# Ulimate.net
KiCad netlist of a schematic drawn in EAGLE
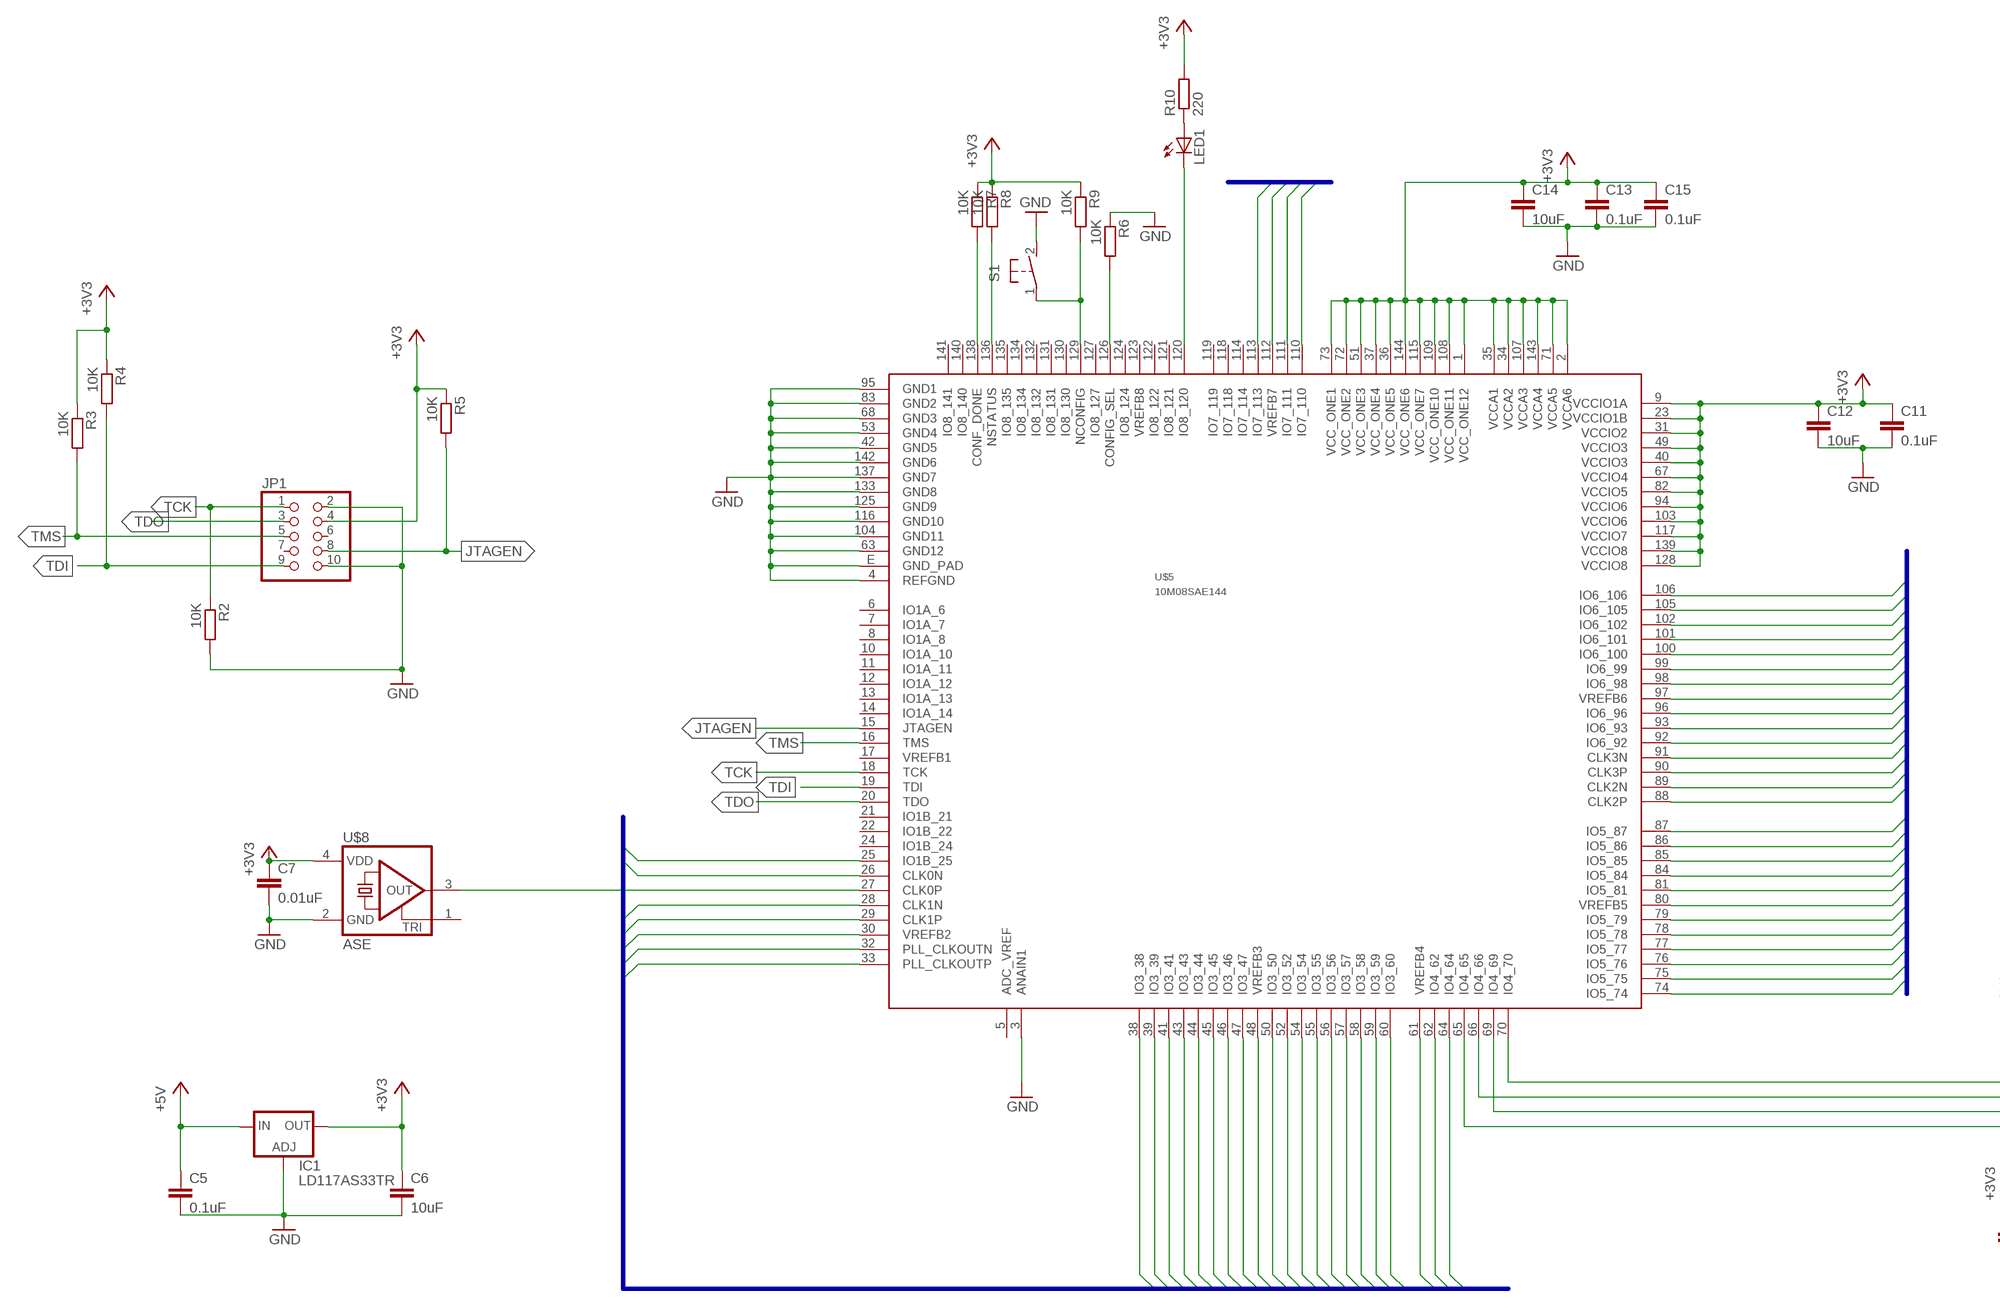
[diagram p0: schematic, sheet 1, part 1 of 2]
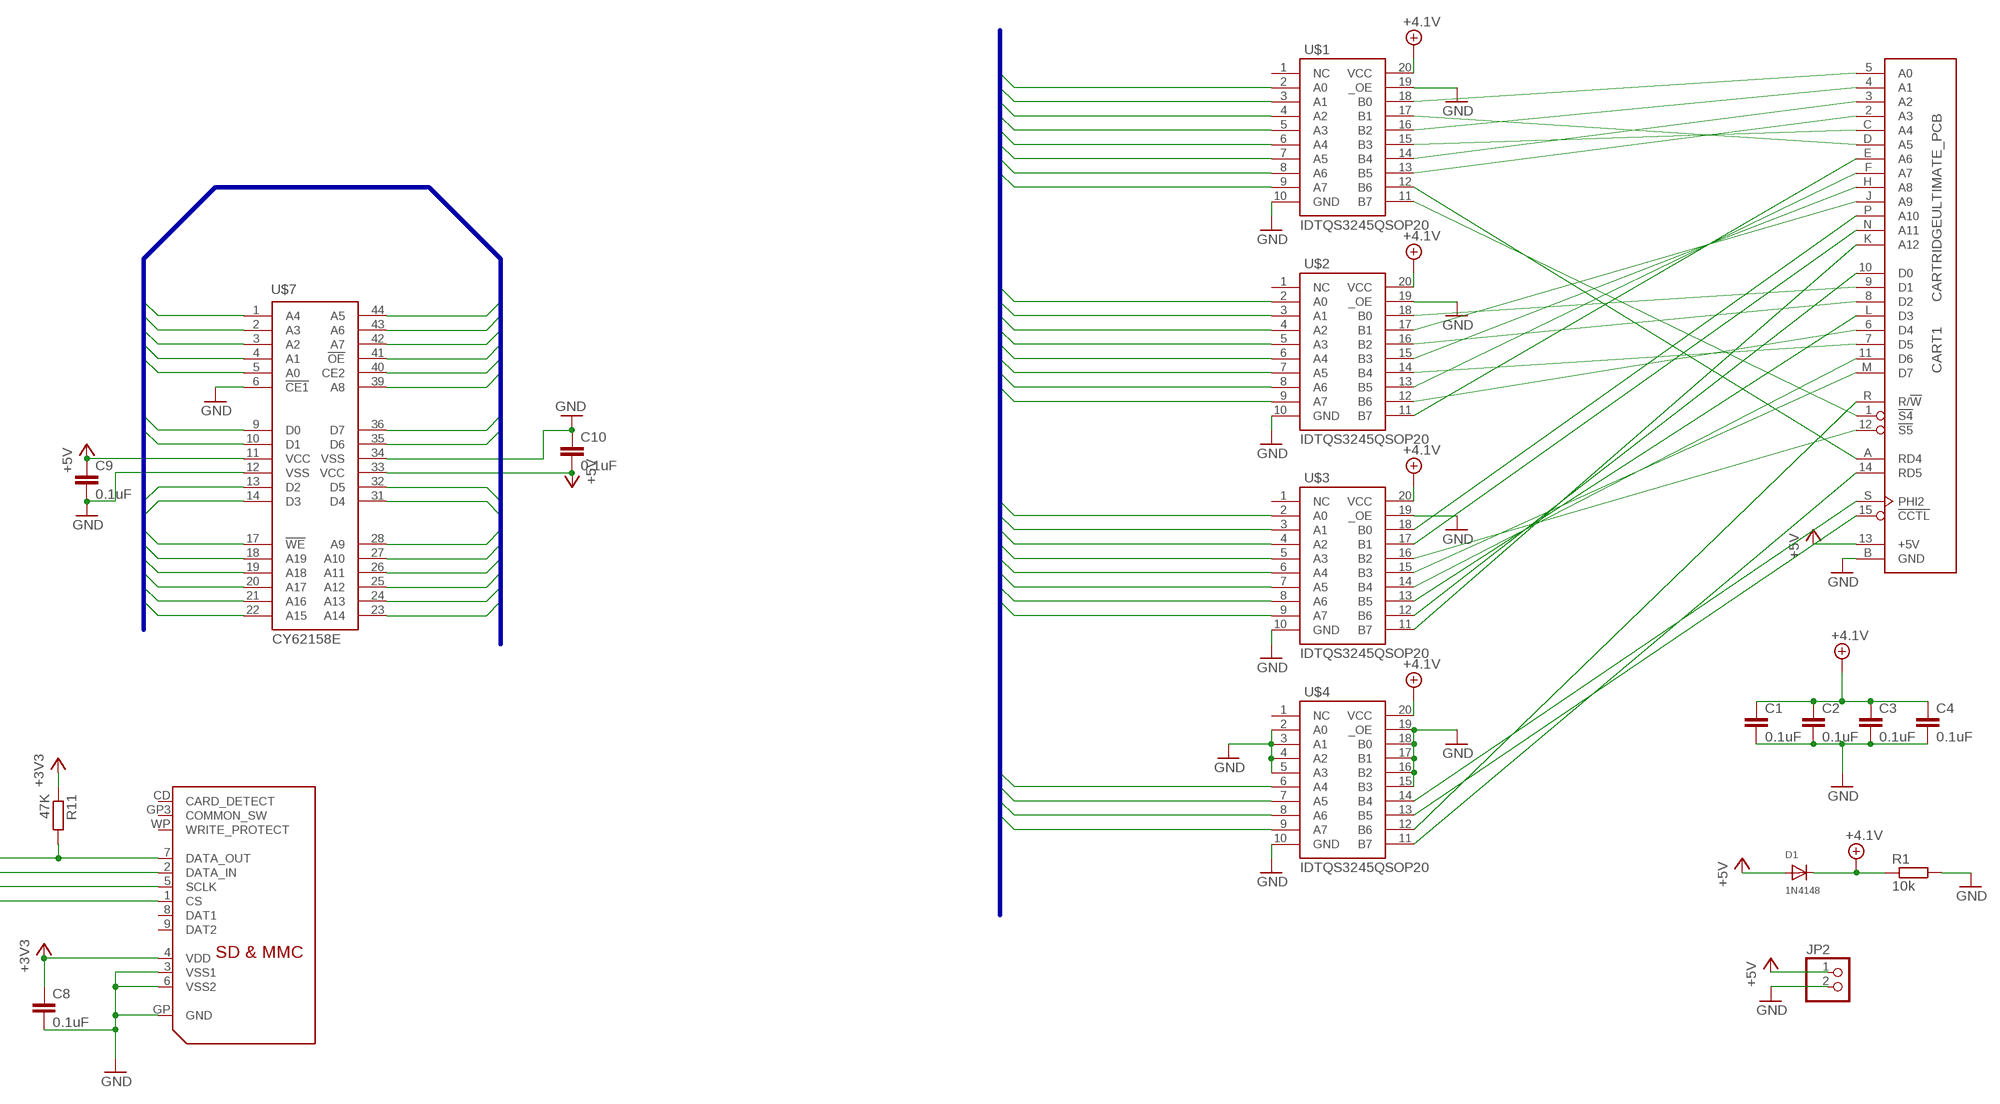
[diagram p1: schematic, sheet 1, part 2 of 2]

(export (version "E")
  (design (tool "Eeschema 10.0.6"))
  (components
    (comp (ref "C1")
      (value "0.1uF")
      (footprint "eagle-import:C0805K")
      (libsource (lib "eagle-import") (part "C-EUC0805K"))
    )
    (comp (ref "C2")
      (value "0.1uF")
      (footprint "eagle-import:C0805K")
      (libsource (lib "eagle-import") (part "C-EUC0805K"))
    )
    (comp (ref "C3")
      (value "0.1uF")
      (footprint "eagle-import:C0805K")
      (libsource (lib "eagle-import") (part "C-EUC0805K"))
    )
    (comp (ref "C4")
      (value "0.1uF")
      (footprint "eagle-import:C0805K")
      (libsource (lib "eagle-import") (part "C-EUC0805K"))
    )
    (comp (ref "C5")
      (value "0.1uF")
      (footprint "eagle-import:C0805K")
      (libsource (lib "eagle-import") (part "C-EUC0805K"))
    )
    (comp (ref "C6")
      (value "10uF")
      (footprint "eagle-import:C0805K")
      (libsource (lib "eagle-import") (part "C-EUC0805K"))
    )
    (comp (ref "C7")
      (value "0.01uF")
      (footprint "eagle-import:C0805K")
      (libsource (lib "eagle-import") (part "C-EUC0805K"))
    )
    (comp (ref "C8")
      (value "0.1uF")
      (footprint "eagle-import:C0805K")
      (libsource (lib "eagle-import") (part "C-EUC0805K"))
    )
    (comp (ref "C9")
      (value "0.1uF")
      (footprint "eagle-import:C0805K")
      (libsource (lib "eagle-import") (part "C-EUC0805K"))
    )
    (comp (ref "C10")
      (value "0.1uF")
      (footprint "eagle-import:C0805K")
      (libsource (lib "eagle-import") (part "C-EUC0805K"))
    )
    (comp (ref "C11")
      (value "0.1uF")
      (footprint "eagle-import:C0805K")
      (libsource (lib "eagle-import") (part "C-EUC0805K"))
    )
    (comp (ref "C12")
      (value "10uF")
      (footprint "eagle-import:C0805K")
      (libsource (lib "eagle-import") (part "C-EUC0805K"))
    )
    (comp (ref "C13")
      (value "0.1uF")
      (footprint "eagle-import:C0805K")
      (libsource (lib "eagle-import") (part "C-EUC0805K"))
    )
    (comp (ref "C14")
      (value "10uF")
      (footprint "eagle-import:C0805K")
      (libsource (lib "eagle-import") (part "C-EUC0805K"))
    )
    (comp (ref "C15")
      (value "0.1uF")
      (footprint "eagle-import:C0805K")
      (libsource (lib "eagle-import") (part "C-EUC0805K"))
    )
    (comp (ref "CART1")
      (value "CARTRIDGEULTIMATE_PCB")
      (footprint "eagle-import:CART_ULTIMATE")
      (libsource (lib "eagle-import") (part "CARTRIDGEULTIMATE_PCB"))
    )
    (comp (ref "D1")
      (value "1N4148")
      (footprint "eagle-import:SOD-123FL")
      (libsource (lib "eagle-import") (part "DIODE_SOD-123FL"))
    )
    (comp (ref "IC1")
      (value "LD117AS33TR")
      (footprint "eagle-import:SOT223")
      (libsource (lib "eagle-import") (part "LD117A?S33TR"))
    )
    (comp (ref "JP1")
      (value "PINHD-2X5")
      (footprint "eagle-import:2X05")
      (libsource (lib "eagle-import") (part "PINHD-2X5"))
    )
    (comp (ref "JP2")
      (value "PINHD-1X2")
      (footprint "eagle-import:1X02")
      (libsource (lib "eagle-import") (part "PINHD-1X2"))
    )
    (comp (ref "LED1")
      (value "LEDSML0805")
      (footprint "eagle-import:SML0805")
      (libsource (lib "eagle-import") (part "LEDSML0805"))
    )
    (comp (ref "R1")
      (value "10k")
      (footprint "eagle-import:R0805")
      (libsource (lib "eagle-import") (part "R-EU_R0805"))
    )
    (comp (ref "R2")
      (value "10K")
      (footprint "eagle-import:R0805")
      (libsource (lib "eagle-import") (part "R-EU_R0805"))
    )
    (comp (ref "R3")
      (value "10K")
      (footprint "eagle-import:R0805")
      (libsource (lib "eagle-import") (part "R-EU_R0805"))
    )
    (comp (ref "R4")
      (value "10K")
      (footprint "eagle-import:R0805")
      (libsource (lib "eagle-import") (part "R-EU_R0805"))
    )
    (comp (ref "R5")
      (value "10K")
      (footprint "eagle-import:R0805")
      (libsource (lib "eagle-import") (part "R-EU_R0805"))
    )
    (comp (ref "R6")
      (value "10K")
      (footprint "eagle-import:R0805")
      (libsource (lib "eagle-import") (part "R-EU_R0805"))
    )
    (comp (ref "R7")
      (value "10K")
      (footprint "eagle-import:R0805")
      (libsource (lib "eagle-import") (part "R-EU_R0805"))
    )
    (comp (ref "R8")
      (value "10K")
      (footprint "eagle-import:R0805")
      (libsource (lib "eagle-import") (part "R-EU_R0805"))
    )
    (comp (ref "R9")
      (value "10K")
      (footprint "eagle-import:R0805")
      (libsource (lib "eagle-import") (part "R-EU_R0805"))
    )
    (comp (ref "R10")
      (value "220")
      (footprint "eagle-import:R0805")
      (libsource (lib "eagle-import") (part "R-EU_R0805"))
    )
    (comp (ref "R11")
      (value "47K")
      (footprint "eagle-import:R0805")
      (libsource (lib "eagle-import") (part "R-EU_R0805"))
    )
    (comp (ref "S1")
      (value "31-XXSKINNY")
      (footprint "eagle-import:B3F-31XX-SKINNIER")
      (libsource (lib "eagle-import") (part "31-XXSKINNY"))
    )
    (comp (ref "U$1")
      (value "IDTQS3245QSOP20")
      (footprint "eagle-import:QSOP20")
      (libsource (lib "eagle-import") (part "IDTQS3245QSOP20"))
    )
    (comp (ref "U$2")
      (value "IDTQS3245QSOP20")
      (footprint "eagle-import:QSOP20")
      (libsource (lib "eagle-import") (part "IDTQS3245QSOP20"))
    )
    (comp (ref "U$3")
      (value "IDTQS3245QSOP20")
      (footprint "eagle-import:QSOP20")
      (libsource (lib "eagle-import") (part "IDTQS3245QSOP20"))
    )
    (comp (ref "U$4")
      (value "IDTQS3245QSOP20")
      (footprint "eagle-import:QSOP20")
      (libsource (lib "eagle-import") (part "IDTQS3245QSOP20"))
    )
    (comp (ref "U$5")
      (value "10M08SAE144")
      (footprint "eagle-import:EQFP144")
      (libsource (lib "eagle-import") (part "10M08SAE144"))
    )
    (comp (ref "U$6")
      (value "SDMMC06132")
      (footprint "eagle-import:06132")
      (libsource (lib "eagle-import") (part "SDMMC06132"))
    )
    (comp (ref "U$7")
      (value "CY62158E")
      (footprint "eagle-import:TSOP44-II")
      (libsource (lib "eagle-import") (part "CY62158E"))
    )
    (comp (ref "U$8")
      (value "ASE")
      (footprint "eagle-import:ASE")
      (libsource (lib "eagle-import") (part "ASE"))
    )
  )
  (nets
    (net (code "1") (name "+3V3") (class "Default")
      (node (ref "C11") (pin "1") (pinfunction "1_1") (pintype "passive"))
      (node (ref "C12") (pin "1") (pinfunction "1_1") (pintype "passive"))
      (node (ref "C13") (pin "1") (pinfunction "1_1") (pintype "passive"))
      (node (ref "C14") (pin "1") (pinfunction "1_1") (pintype "passive"))
      (node (ref "C15") (pin "1") (pinfunction "1_1") (pintype "passive"))
      (node (ref "C6") (pin "1") (pinfunction "1_1") (pintype "passive"))
      (node (ref "C7") (pin "1") (pinfunction "1_1") (pintype "passive"))
      (node (ref "C8") (pin "1") (pinfunction "1_1") (pintype "passive"))
      (node (ref "IC1") (pin "4") (pinfunction "OUT_4") (pintype "passive"))
      (node (ref "JP1") (pin "4") (pinfunction "4_4") (pintype "passive"))
      (node (ref "R10") (pin "2") (pinfunction "2_2") (pintype "passive"))
      (node (ref "R11") (pin "1") (pinfunction "1_1") (pintype "passive"))
      (node (ref "R3") (pin "1") (pinfunction "1_1") (pintype "passive"))
      (node (ref "R4") (pin "1") (pinfunction "1_1") (pintype "passive"))
      (node (ref "R5") (pin "1") (pinfunction "1_1") (pintype "passive"))
      (node (ref "R7") (pin "1") (pinfunction "1_1") (pintype "passive"))
      (node (ref "R8") (pin "1") (pinfunction "1_1") (pintype "passive"))
      (node (ref "R9") (pin "1") (pinfunction "1_1") (pintype "passive"))
      (node (ref "U$5") (pin "1") (pinfunction "VCC_ONE12_1") (pintype "bidirectional"))
      (node (ref "U$5") (pin "103") (pinfunction "VCCIO6_103") (pintype "bidirectional"))
      (node (ref "U$5") (pin "107") (pinfunction "VCCA3_107") (pintype "bidirectional"))
      (node (ref "U$5") (pin "108") (pinfunction "VCC_ONE11_108") (pintype "bidirectional"))
      (node (ref "U$5") (pin "109") (pinfunction "VCC_ONE10_109") (pintype "bidirectional"))
      (node (ref "U$5") (pin "115") (pinfunction "VCC_ONE7_115") (pintype "bidirectional"))
      (node (ref "U$5") (pin "117") (pinfunction "VCCIO7_117") (pintype "bidirectional"))
      (node (ref "U$5") (pin "128") (pinfunction "VCCIO8_128") (pintype "bidirectional"))
      (node (ref "U$5") (pin "139") (pinfunction "VCCIO8_139") (pintype "bidirectional"))
      (node (ref "U$5") (pin "143") (pinfunction "VCCA4_143") (pintype "bidirectional"))
      (node (ref "U$5") (pin "144") (pinfunction "VCC_ONE6_144") (pintype "bidirectional"))
      (node (ref "U$5") (pin "2") (pinfunction "VCCA6_2") (pintype "bidirectional"))
      (node (ref "U$5") (pin "23") (pinfunction "VCCIO1B_23") (pintype "bidirectional"))
      (node (ref "U$5") (pin "31") (pinfunction "VCCIO2_31") (pintype "bidirectional"))
      (node (ref "U$5") (pin "34") (pinfunction "VCCA2_34") (pintype "bidirectional"))
      (node (ref "U$5") (pin "35") (pinfunction "VCCA1_35") (pintype "bidirectional"))
      (node (ref "U$5") (pin "36") (pinfunction "VCC_ONE5_36") (pintype "bidirectional"))
      (node (ref "U$5") (pin "37") (pinfunction "VCC_ONE4_37") (pintype "bidirectional"))
      (node (ref "U$5") (pin "40") (pinfunction "VCCIO3_40") (pintype "bidirectional"))
      (node (ref "U$5") (pin "49") (pinfunction "VCCIO3_49") (pintype "bidirectional"))
      (node (ref "U$5") (pin "51") (pinfunction "VCC_ONE3_51") (pintype "bidirectional"))
      (node (ref "U$5") (pin "67") (pinfunction "VCCIO4_67") (pintype "bidirectional"))
      (node (ref "U$5") (pin "71") (pinfunction "VCCA5_71") (pintype "bidirectional"))
      (node (ref "U$5") (pin "72") (pinfunction "VCC_ONE2_72") (pintype "bidirectional"))
      (node (ref "U$5") (pin "73") (pinfunction "VCC_ONE1_73") (pintype "bidirectional"))
      (node (ref "U$5") (pin "82") (pinfunction "VCCIO5_82") (pintype "bidirectional"))
      (node (ref "U$5") (pin "9") (pinfunction "VCCIO1A_9") (pintype "bidirectional"))
      (node (ref "U$5") (pin "94") (pinfunction "VCCIO6_94") (pintype "bidirectional"))
      (node (ref "U$6") (pin "4") (pinfunction "VDD_4") (pintype "power_in"))
      (node (ref "U$8") (pin "4") (pinfunction "VDD_4") (pintype "power_in"))
    )
    (net (code "2") (name "+4.1V") (class "Default")
      (node (ref "C1") (pin "1") (pinfunction "1_1") (pintype "passive"))
      (node (ref "C2") (pin "1") (pinfunction "1_1") (pintype "passive"))
      (node (ref "C3") (pin "1") (pinfunction "1_1") (pintype "passive"))
      (node (ref "C4") (pin "1") (pinfunction "1_1") (pintype "passive"))
      (node (ref "D1") (pin "C") (pinfunction "C_C") (pintype "passive"))
      (node (ref "R1") (pin "1") (pinfunction "1_1") (pintype "passive"))
      (node (ref "U$1") (pin "20") (pinfunction "VCC_20") (pintype "power_in"))
      (node (ref "U$2") (pin "20") (pinfunction "VCC_20") (pintype "power_in"))
      (node (ref "U$3") (pin "20") (pinfunction "VCC_20") (pintype "power_in"))
      (node (ref "U$4") (pin "20") (pinfunction "VCC_20") (pintype "power_in"))
    )
    (net (code "3") (name "+5V") (class "Default")
      (node (ref "C10") (pin "2") (pinfunction "2_2") (pintype "passive"))
      (node (ref "C5") (pin "1") (pinfunction "1_1") (pintype "passive"))
      (node (ref "C9") (pin "1") (pinfunction "1_1") (pintype "passive"))
      (node (ref "CART1") (pin "13") (pinfunction "+5V_13") (pintype "power_in"))
      (node (ref "D1") (pin "A") (pinfunction "A_A") (pintype "passive"))
      (node (ref "IC1") (pin "3") (pinfunction "IN_3") (pintype "input"))
      (node (ref "JP2") (pin "1") (pinfunction "1_1") (pintype "passive"))
      (node (ref "U$7") (pin "11") (pinfunction "VCC_11") (pintype "bidirectional"))
      (node (ref "U$7") (pin "33") (pinfunction "VCC_33") (pintype "bidirectional"))
    )
    (net (code "4") (name "/A0") (class "Default")
      (node (ref "U$5") (pin "96") (pinfunction "IO6_96_96") (pintype "bidirectional"))
      (node (ref "U$7") (pin "5") (pinfunction "A0_5") (pintype "bidirectional"))
    )
    (net (code "5") (name "/A1") (class "Default")
      (node (ref "U$5") (pin "97") (pinfunction "VREFB6_97") (pintype "bidirectional"))
      (node (ref "U$7") (pin "4") (pinfunction "A1_4") (pintype "bidirectional"))
    )
    (net (code "6") (name "/A2") (class "Default")
      (node (ref "U$5") (pin "98") (pinfunction "IO6_98_98") (pintype "bidirectional"))
      (node (ref "U$7") (pin "3") (pinfunction "A2_3") (pintype "bidirectional"))
    )
    (net (code "7") (name "/A3") (class "Default")
      (node (ref "U$5") (pin "99") (pinfunction "IO6_99_99") (pintype "bidirectional"))
      (node (ref "U$7") (pin "2") (pinfunction "A3_2") (pintype "bidirectional"))
    )
    (net (code "8") (name "/A4") (class "Default")
      (node (ref "U$5") (pin "100") (pinfunction "IO6_100_100") (pintype "bidirectional"))
      (node (ref "U$7") (pin "1") (pinfunction "A4_1") (pintype "bidirectional"))
    )
    (net (code "9") (name "/A5") (class "Default")
      (node (ref "U$5") (pin "105") (pinfunction "IO6_105_105") (pintype "bidirectional"))
      (node (ref "U$7") (pin "44") (pinfunction "A5_44") (pintype "bidirectional"))
    )
    (net (code "10") (name "/A6") (class "Default")
      (node (ref "U$5") (pin "102") (pinfunction "IO6_102_102") (pintype "bidirectional"))
      (node (ref "U$7") (pin "43") (pinfunction "A6_43") (pintype "bidirectional"))
    )
    (net (code "11") (name "/A7") (class "Default")
      (node (ref "U$5") (pin "101") (pinfunction "IO6_101_101") (pintype "bidirectional"))
      (node (ref "U$7") (pin "42") (pinfunction "A7_42") (pintype "bidirectional"))
    )
    (net (code "12") (name "/A8") (class "Default")
      (node (ref "U$5") (pin "111") (pinfunction "IO7_111_111") (pintype "bidirectional"))
      (node (ref "U$7") (pin "39") (pinfunction "A8_39") (pintype "bidirectional"))
    )
    (net (code "13") (name "/A9") (class "Default")
      (node (ref "U$5") (pin "76") (pinfunction "IO5_76_76") (pintype "bidirectional"))
      (node (ref "U$7") (pin "28") (pinfunction "A9_28") (pintype "bidirectional"))
    )
    (net (code "14") (name "/A10") (class "Default")
      (node (ref "U$5") (pin "77") (pinfunction "IO5_77_77") (pintype "bidirectional"))
      (node (ref "U$7") (pin "27") (pinfunction "A10_27") (pintype "bidirectional"))
    )
    (net (code "15") (name "/A11") (class "Default")
      (node (ref "U$5") (pin "78") (pinfunction "IO5_78_78") (pintype "bidirectional"))
      (node (ref "U$7") (pin "26") (pinfunction "A11_26") (pintype "bidirectional"))
    )
    (net (code "16") (name "/A12") (class "Default")
      (node (ref "U$5") (pin "79") (pinfunction "IO5_79_79") (pintype "bidirectional"))
      (node (ref "U$7") (pin "25") (pinfunction "A12_25") (pintype "bidirectional"))
    )
    (net (code "17") (name "/A13") (class "Default")
      (node (ref "U$5") (pin "80") (pinfunction "VREFB5_80") (pintype "bidirectional"))
      (node (ref "U$7") (pin "24") (pinfunction "A13_24") (pintype "bidirectional"))
    )
    (net (code "18") (name "/A14") (class "Default")
      (node (ref "U$5") (pin "81") (pinfunction "IO5_81_81") (pintype "bidirectional"))
      (node (ref "U$7") (pin "23") (pinfunction "A14_23") (pintype "bidirectional"))
    )
    (net (code "19") (name "/A15") (class "Default")
      (node (ref "U$5") (pin "84") (pinfunction "IO5_84_84") (pintype "bidirectional"))
      (node (ref "U$7") (pin "22") (pinfunction "A15_22") (pintype "bidirectional"))
    )
    (net (code "20") (name "/A16") (class "Default")
      (node (ref "U$5") (pin "85") (pinfunction "IO5_85_85") (pintype "bidirectional"))
      (node (ref "U$7") (pin "21") (pinfunction "A16_21") (pintype "bidirectional"))
    )
    (net (code "21") (name "/A17") (class "Default")
      (node (ref "U$5") (pin "86") (pinfunction "IO5_86_86") (pintype "bidirectional"))
      (node (ref "U$7") (pin "20") (pinfunction "A17_20") (pintype "bidirectional"))
    )
    (net (code "22") (name "/A18") (class "Default")
      (node (ref "U$5") (pin "87") (pinfunction "IO5_87_87") (pintype "bidirectional"))
      (node (ref "U$7") (pin "19") (pinfunction "A18_19") (pintype "bidirectional"))
    )
    (net (code "23") (name "/A19") (class "Default")
      (node (ref "U$5") (pin "88") (pinfunction "CLK2P_88") (pintype "bidirectional"))
      (node (ref "U$7") (pin "18") (pinfunction "A19_18") (pintype "bidirectional"))
    )
    (net (code "24") (name "/CART_A0") (class "Default")
      (node (ref "U$1") (pin "2") (pinfunction "A0_2") (pintype "bidirectional"))
      (node (ref "U$5") (pin "39") (pinfunction "IO3_39_39") (pintype "bidirectional"))
    )
    (net (code "25") (name "/CART_A1") (class "Default")
      (node (ref "U$1") (pin "4") (pinfunction "A2_4") (pintype "bidirectional"))
      (node (ref "U$5") (pin "33") (pinfunction "PLL_CLKOUTP_33") (pintype "bidirectional"))
    )
    (net (code "26") (name "/CART_A2") (class "Default")
      (node (ref "U$1") (pin "6") (pinfunction "A4_6") (pintype "bidirectional"))
      (node (ref "U$5") (pin "30") (pinfunction "VREFB2_30") (pintype "bidirectional"))
    )
    (net (code "27") (name "/CART_A3") (class "Default")
      (node (ref "U$1") (pin "7") (pinfunction "A5_7") (pintype "bidirectional"))
      (node (ref "U$5") (pin "29") (pinfunction "CLK1P_29") (pintype "bidirectional"))
    )
    (net (code "28") (name "/CART_A4") (class "Default")
      (node (ref "U$1") (pin "5") (pinfunction "A3_5") (pintype "bidirectional"))
      (node (ref "U$5") (pin "32") (pinfunction "PLL_CLKOUTN_32") (pintype "bidirectional"))
    )
    (net (code "29") (name "/CART_A5") (class "Default")
      (node (ref "U$1") (pin "3") (pinfunction "A1_3") (pintype "bidirectional"))
      (node (ref "U$5") (pin "38") (pinfunction "IO3_38_38") (pintype "bidirectional"))
    )
    (net (code "30") (name "/CART_A6") (class "Default")
      (node (ref "U$2") (pin "9") (pinfunction "A7_9") (pintype "bidirectional"))
      (node (ref "U$5") (pin "41") (pinfunction "IO3_41_41") (pintype "bidirectional"))
    )
    (net (code "31") (name "/CART_A7") (class "Default")
      (node (ref "U$2") (pin "7") (pinfunction "A5_7") (pintype "bidirectional"))
      (node (ref "U$5") (pin "44") (pinfunction "IO3_44_44") (pintype "bidirectional"))
    )
    (net (code "32") (name "/CART_A8") (class "Default")
      (node (ref "U$2") (pin "5") (pinfunction "A3_5") (pintype "bidirectional"))
      (node (ref "U$5") (pin "46") (pinfunction "IO3_46_46") (pintype "bidirectional"))
    )
    (net (code "33") (name "/CART_A9") (class "Default")
      (node (ref "U$2") (pin "3") (pinfunction "A1_3") (pintype "bidirectional"))
      (node (ref "U$5") (pin "48") (pinfunction "VREFB3_48") (pintype "bidirectional"))
    )
    (net (code "34") (name "/CART_A10") (class "Default")
      (node (ref "U$3") (pin "2") (pinfunction "A0_2") (pintype "bidirectional"))
      (node (ref "U$5") (pin "60") (pinfunction "IO3_60_60") (pintype "bidirectional"))
    )
    (net (code "35") (name "/CART_A11") (class "Default")
      (node (ref "U$3") (pin "3") (pinfunction "A1_3") (pintype "bidirectional"))
      (node (ref "U$5") (pin "59") (pinfunction "IO3_59_59") (pintype "bidirectional"))
    )
    (net (code "36") (name "/CART_A12") (class "Default")
      (node (ref "U$3") (pin "9") (pinfunction "A7_9") (pintype "bidirectional"))
      (node (ref "U$5") (pin "52") (pinfunction "IO3_52_52") (pintype "bidirectional"))
    )
    (net (code "37") (name "/CART_CTL") (class "Default")
      (node (ref "U$4") (pin "7") (pinfunction "A5_7") (pintype "bidirectional"))
      (node (ref "U$5") (pin "64") (pinfunction "IO4_64_64") (pintype "bidirectional"))
    )
    (net (code "38") (name "/CART_D0") (class "Default")
      (node (ref "U$3") (pin "8") (pinfunction "A6_8") (pintype "bidirectional"))
      (node (ref "U$5") (pin "54") (pinfunction "IO3_54_54") (pintype "bidirectional"))
    )
    (net (code "39") (name "/CART_D1") (class "Default")
      (node (ref "U$2") (pin "2") (pinfunction "A0_2") (pintype "bidirectional"))
      (node (ref "U$5") (pin "50") (pinfunction "IO3_50_50") (pintype "bidirectional"))
    )
    (net (code "40") (name "/CART_D2") (class "Default")
      (node (ref "U$2") (pin "4") (pinfunction "A2_4") (pintype "bidirectional"))
      (node (ref "U$5") (pin "47") (pinfunction "IO3_47_47") (pintype "bidirectional"))
    )
    (net (code "41") (name "/CART_D3") (class "Default")
      (node (ref "U$3") (pin "7") (pinfunction "A5_7") (pintype "bidirectional"))
      (node (ref "U$5") (pin "55") (pinfunction "IO3_55_55") (pintype "bidirectional"))
    )
    (net (code "42") (name "/CART_D4") (class "Default")
      (node (ref "U$2") (pin "8") (pinfunction "A6_8") (pintype "bidirectional"))
      (node (ref "U$5") (pin "43") (pinfunction "IO3_43_43") (pintype "bidirectional"))
    )
    (net (code "43") (name "/CART_D5") (class "Default")
      (node (ref "U$2") (pin "6") (pinfunction "A4_6") (pintype "bidirectional"))
      (node (ref "U$5") (pin "45") (pinfunction "IO3_45_45") (pintype "bidirectional"))
    )
    (net (code "44") (name "/CART_D6") (class "Default")
      (node (ref "U$3") (pin "6") (pinfunction "A4_6") (pintype "bidirectional"))
      (node (ref "U$5") (pin "56") (pinfunction "IO3_56_56") (pintype "bidirectional"))
    )
    (net (code "45") (name "/CART_D7") (class "Default")
      (node (ref "U$3") (pin "5") (pinfunction "A3_5") (pintype "bidirectional"))
      (node (ref "U$5") (pin "57") (pinfunction "IO3_57_57") (pintype "bidirectional"))
    )
    (net (code "46") (name "/CART_PHI") (class "Default")
      (node (ref "U$4") (pin "6") (pinfunction "A4_6") (pintype "bidirectional"))
      (node (ref "U$5") (pin "26") (pinfunction "CLK0N_26") (pintype "bidirectional"))
    )
    (net (code "47") (name "/CART_RD4") (class "Default")
      (node (ref "U$1") (pin "8") (pinfunction "A6_8") (pintype "bidirectional"))
      (node (ref "U$5") (pin "25") (pinfunction "IO1B_25_25") (pintype "bidirectional"))
    )
    (net (code "48") (name "/CART_RD5") (class "Default")
      (node (ref "U$4") (pin "9") (pinfunction "A7_9") (pintype "bidirectional"))
      (node (ref "U$5") (pin "61") (pinfunction "VREFB4_61") (pintype "bidirectional"))
    )
    (net (code "49") (name "/CART_RW") (class "Default")
      (node (ref "U$4") (pin "8") (pinfunction "A6_8") (pintype "bidirectional"))
      (node (ref "U$5") (pin "62") (pinfunction "IO4_62_62") (pintype "bidirectional"))
    )
    (net (code "50") (name "/CART_S4") (class "Default")
      (node (ref "U$1") (pin "9") (pinfunction "A7_9") (pintype "bidirectional"))
      (node (ref "U$5") (pin "28") (pinfunction "CLK1N_28") (pintype "bidirectional"))
    )
    (net (code "51") (name "/CART_S5") (class "Default")
      (node (ref "U$3") (pin "4") (pinfunction "A2_4") (pintype "bidirectional"))
      (node (ref "U$5") (pin "58") (pinfunction "IO3_58_58") (pintype "bidirectional"))
    )
    (net (code "52") (name "/CE") (class "Default")
      (node (ref "U$5") (pin "110") (pinfunction "IO7_110_110") (pintype "bidirectional"))
      (node (ref "U$7") (pin "40") (pinfunction "CE2_40") (pintype "bidirectional"))
    )
    (net (code "53") (name "/D0") (class "Default")
      (node (ref "U$5") (pin "93") (pinfunction "IO6_93_93") (pintype "bidirectional"))
      (node (ref "U$7") (pin "9") (pinfunction "D0_9") (pintype "bidirectional"))
    )
    (net (code "54") (name "/D1") (class "Default")
      (node (ref "U$5") (pin "92") (pinfunction "IO6_92_92") (pintype "bidirectional"))
      (node (ref "U$7") (pin "10") (pinfunction "D1_10") (pintype "bidirectional"))
    )
    (net (code "55") (name "/D2") (class "Default")
      (node (ref "U$5") (pin "91") (pinfunction "CLK3N_91") (pintype "bidirectional"))
      (node (ref "U$7") (pin "13") (pinfunction "D2_13") (pintype "bidirectional"))
    )
    (net (code "56") (name "/D3") (class "Default")
      (node (ref "U$5") (pin "90") (pinfunction "CLK3P_90") (pintype "bidirectional"))
      (node (ref "U$7") (pin "14") (pinfunction "D3_14") (pintype "bidirectional"))
    )
    (net (code "57") (name "/D4") (class "Default")
      (node (ref "U$5") (pin "75") (pinfunction "IO5_75_75") (pintype "bidirectional"))
      (node (ref "U$7") (pin "31") (pinfunction "D4_31") (pintype "bidirectional"))
    )
    (net (code "58") (name "/D5") (class "Default")
      (node (ref "U$5") (pin "74") (pinfunction "IO5_74_74") (pintype "bidirectional"))
      (node (ref "U$7") (pin "32") (pinfunction "D5_32") (pintype "bidirectional"))
    )
    (net (code "59") (name "/D6") (class "Default")
      (node (ref "U$5") (pin "113") (pinfunction "IO7_113_113") (pintype "bidirectional"))
      (node (ref "U$7") (pin "35") (pinfunction "D6_35") (pintype "bidirectional"))
    )
    (net (code "60") (name "/D7") (class "Default")
      (node (ref "U$5") (pin "112") (pinfunction "VREFB7_112") (pintype "bidirectional"))
      (node (ref "U$7") (pin "36") (pinfunction "D7_36") (pintype "bidirectional"))
    )
    (net (code "63") (name "/~{OE}") (class "Default")
      (node (ref "U$5") (pin "106") (pinfunction "IO6_106_106") (pintype "bidirectional"))
      (node (ref "U$7") (pin "41") (pinfunction "~{OE}_41") (pintype "bidirectional"))
    )
    (net (code "64") (name "/~{WE}") (class "Default")
      (node (ref "U$5") (pin "89") (pinfunction "CLK2N_89") (pintype "bidirectional"))
      (node (ref "U$7") (pin "17") (pinfunction "~{WE}_17") (pintype "bidirectional"))
    )
    (net (code "65") (name "GND") (class "Default")
      (node (ref "C1") (pin "2") (pinfunction "2_2") (pintype "passive"))
      (node (ref "C10") (pin "1") (pinfunction "1_1") (pintype "passive"))
      (node (ref "C11") (pin "2") (pinfunction "2_2") (pintype "passive"))
      (node (ref "C12") (pin "2") (pinfunction "2_2") (pintype "passive"))
      (node (ref "C13") (pin "2") (pinfunction "2_2") (pintype "passive"))
      (node (ref "C14") (pin "2") (pinfunction "2_2") (pintype "passive"))
      (node (ref "C15") (pin "2") (pinfunction "2_2") (pintype "passive"))
      (node (ref "C2") (pin "2") (pinfunction "2_2") (pintype "passive"))
      (node (ref "C3") (pin "2") (pinfunction "2_2") (pintype "passive"))
      (node (ref "C4") (pin "2") (pinfunction "2_2") (pintype "passive"))
      (node (ref "C5") (pin "2") (pinfunction "2_2") (pintype "passive"))
      (node (ref "C6") (pin "2") (pinfunction "2_2") (pintype "passive"))
      (node (ref "C7") (pin "2") (pinfunction "2_2") (pintype "passive"))
      (node (ref "C8") (pin "2") (pinfunction "2_2") (pintype "passive"))
      (node (ref "C9") (pin "2") (pinfunction "2_2") (pintype "passive"))
      (node (ref "CART1") (pin "B") (pinfunction "GND_B") (pintype "power_in"))
      (node (ref "IC1") (pin "1") (pinfunction "ADJ_1") (pintype "input"))
      (node (ref "JP1") (pin "10") (pinfunction "10_10") (pintype "passive"))
      (node (ref "JP1") (pin "2") (pinfunction "2_2") (pintype "passive"))
      (node (ref "JP2") (pin "2") (pinfunction "2_2") (pintype "passive"))
      (node (ref "R1") (pin "2") (pinfunction "2_2") (pintype "passive"))
      (node (ref "R2") (pin "2") (pinfunction "2_2") (pintype "passive"))
      (node (ref "R6") (pin "1") (pinfunction "1_1") (pintype "passive"))
      (node (ref "S1") (pin "2") (pinfunction "S_2") (pintype "passive"))
      (node (ref "U$1") (pin "10") (pinfunction "GND_10") (pintype "power_in"))
      (node (ref "U$1") (pin "19") (pinfunction "_OE_19") (pintype "bidirectional"))
      (node (ref "U$2") (pin "10") (pinfunction "GND_10") (pintype "power_in"))
      (node (ref "U$2") (pin "19") (pinfunction "_OE_19") (pintype "bidirectional"))
      (node (ref "U$3") (pin "10") (pinfunction "GND_10") (pintype "power_in"))
      (node (ref "U$3") (pin "19") (pinfunction "_OE_19") (pintype "bidirectional"))
      (node (ref "U$4") (pin "10") (pinfunction "GND_10") (pintype "power_in"))
      (node (ref "U$4") (pin "15") (pinfunction "B3_15") (pintype "bidirectional"))
      (node (ref "U$4") (pin "16") (pinfunction "B2_16") (pintype "bidirectional"))
      (node (ref "U$4") (pin "17") (pinfunction "B1_17") (pintype "bidirectional"))
      (node (ref "U$4") (pin "18") (pinfunction "B0_18") (pintype "bidirectional"))
      (node (ref "U$4") (pin "19") (pinfunction "_OE_19") (pintype "bidirectional"))
      (node (ref "U$4") (pin "2") (pinfunction "A0_2") (pintype "bidirectional"))
      (node (ref "U$4") (pin "3") (pinfunction "A1_3") (pintype "bidirectional"))
      (node (ref "U$4") (pin "4") (pinfunction "A2_4") (pintype "bidirectional"))
      (node (ref "U$4") (pin "5") (pinfunction "A3_5") (pintype "bidirectional"))
      (node (ref "U$5") (pin "104") (pinfunction "GND11_104") (pintype "bidirectional"))
      (node (ref "U$5") (pin "116") (pinfunction "GND10_116") (pintype "bidirectional"))
      (node (ref "U$5") (pin "125") (pinfunction "GND9_125") (pintype "bidirectional"))
      (node (ref "U$5") (pin "133") (pinfunction "GND8_133") (pintype "bidirectional"))
      (node (ref "U$5") (pin "137") (pinfunction "GND7_137") (pintype "bidirectional"))
      (node (ref "U$5") (pin "142") (pinfunction "GND6_142") (pintype "bidirectional"))
      (node (ref "U$5") (pin "3") (pinfunction "ANAIN1_3") (pintype "bidirectional"))
      (node (ref "U$5") (pin "4") (pinfunction "REFGND_4") (pintype "bidirectional"))
      (node (ref "U$5") (pin "42") (pinfunction "GND5_42") (pintype "bidirectional"))
      (node (ref "U$5") (pin "53") (pinfunction "GND4_53") (pintype "bidirectional"))
      (node (ref "U$5") (pin "63") (pinfunction "GND12_63") (pintype "bidirectional"))
      (node (ref "U$5") (pin "68") (pinfunction "GND3_68") (pintype "bidirectional"))
      (node (ref "U$5") (pin "83") (pinfunction "GND2_83") (pintype "bidirectional"))
      (node (ref "U$5") (pin "95") (pinfunction "GND1_95") (pintype "bidirectional"))
      (node (ref "U$5") (pin "E") (pinfunction "GND_PAD_E") (pintype "bidirectional"))
      (node (ref "U$6") (pin "3") (pinfunction "VSS1_3") (pintype "power_in"))
      (node (ref "U$6") (pin "6") (pinfunction "VSS2_6") (pintype "power_in"))
      (node (ref "U$6") (pin "GP") (pinfunction "GND_GP") (pintype "power_in"))
      (node (ref "U$7") (pin "12") (pinfunction "VSS_12") (pintype "bidirectional"))
      (node (ref "U$7") (pin "34") (pinfunction "VSS_34") (pintype "bidirectional"))
      (node (ref "U$7") (pin "6") (pinfunction "~{CE1}_6") (pintype "bidirectional"))
      (node (ref "U$8") (pin "2") (pinfunction "GND_2") (pintype "power_in"))
    )
    (net (code "66") (name "JTAGEN") (class "Default")
      (node (ref "JP1") (pin "8") (pinfunction "8_8") (pintype "passive"))
      (node (ref "R5") (pin "2") (pinfunction "2_2") (pintype "passive"))
      (node (ref "U$5") (pin "15") (pinfunction "JTAGEN_15") (pintype "bidirectional"))
    )
    (net (code "67") (name "Net-(CART1-A0)") (class "Default")
      (node (ref "CART1") (pin "5") (pinfunction "A0_5") (pintype "output"))
      (node (ref "U$1") (pin "18") (pinfunction "B0_18") (pintype "bidirectional"))
    )
    (net (code "68") (name "Net-(CART1-A1)") (class "Default")
      (node (ref "CART1") (pin "4") (pinfunction "A1_4") (pintype "output"))
      (node (ref "U$1") (pin "16") (pinfunction "B2_16") (pintype "bidirectional"))
    )
    (net (code "69") (name "Net-(CART1-A2)") (class "Default")
      (node (ref "CART1") (pin "3") (pinfunction "A2_3") (pintype "output"))
      (node (ref "U$1") (pin "14") (pinfunction "B4_14") (pintype "bidirectional"))
    )
    (net (code "70") (name "Net-(CART1-A3)") (class "Default")
      (node (ref "CART1") (pin "2") (pinfunction "A3_2") (pintype "output"))
      (node (ref "U$1") (pin "13") (pinfunction "B5_13") (pintype "bidirectional"))
    )
    (net (code "71") (name "Net-(CART1-A4)") (class "Default")
      (node (ref "CART1") (pin "C") (pinfunction "A4_C") (pintype "output"))
      (node (ref "U$1") (pin "15") (pinfunction "B3_15") (pintype "bidirectional"))
    )
    (net (code "72") (name "Net-(CART1-A5)") (class "Default")
      (node (ref "CART1") (pin "D") (pinfunction "A5_D") (pintype "output"))
      (node (ref "U$1") (pin "17") (pinfunction "B1_17") (pintype "bidirectional"))
    )
    (net (code "73") (name "Net-(CART1-A6)") (class "Default")
      (node (ref "CART1") (pin "E") (pinfunction "A6_E") (pintype "output"))
      (node (ref "U$2") (pin "11") (pinfunction "B7_11") (pintype "bidirectional"))
    )
    (net (code "74") (name "Net-(CART1-A7)") (class "Default")
      (node (ref "CART1") (pin "F") (pinfunction "A7_F") (pintype "output"))
      (node (ref "U$2") (pin "13") (pinfunction "B5_13") (pintype "bidirectional"))
    )
    (net (code "75") (name "Net-(CART1-A8)") (class "Default")
      (node (ref "CART1") (pin "H") (pinfunction "A8_H") (pintype "output"))
      (node (ref "U$2") (pin "15") (pinfunction "B3_15") (pintype "bidirectional"))
    )
    (net (code "76") (name "Net-(CART1-A9)") (class "Default")
      (node (ref "CART1") (pin "J") (pinfunction "A9_J") (pintype "output"))
      (node (ref "U$2") (pin "17") (pinfunction "B1_17") (pintype "bidirectional"))
    )
    (net (code "77") (name "Net-(CART1-A10)") (class "Default")
      (node (ref "CART1") (pin "P") (pinfunction "A10_P") (pintype "output"))
      (node (ref "U$3") (pin "18") (pinfunction "B0_18") (pintype "bidirectional"))
    )
    (net (code "78") (name "Net-(CART1-A11)") (class "Default")
      (node (ref "CART1") (pin "N") (pinfunction "A11_N") (pintype "output"))
      (node (ref "U$3") (pin "17") (pinfunction "B1_17") (pintype "bidirectional"))
    )
    (net (code "79") (name "Net-(CART1-A12)") (class "Default")
      (node (ref "CART1") (pin "K") (pinfunction "A12_K") (pintype "output"))
      (node (ref "U$3") (pin "11") (pinfunction "B7_11") (pintype "bidirectional"))
    )
    (net (code "80") (name "Net-(CART1-D0)") (class "Default")
      (node (ref "CART1") (pin "10") (pinfunction "D0_10") (pintype "bidirectional"))
      (node (ref "U$3") (pin "12") (pinfunction "B6_12") (pintype "bidirectional"))
    )
    (net (code "81") (name "Net-(CART1-D1)") (class "Default")
      (node (ref "CART1") (pin "9") (pinfunction "D1_9") (pintype "bidirectional"))
      (node (ref "U$2") (pin "18") (pinfunction "B0_18") (pintype "bidirectional"))
    )
    (net (code "82") (name "Net-(CART1-D2)") (class "Default")
      (node (ref "CART1") (pin "8") (pinfunction "D2_8") (pintype "bidirectional"))
      (node (ref "U$2") (pin "16") (pinfunction "B2_16") (pintype "bidirectional"))
    )
    (net (code "83") (name "Net-(CART1-D3)") (class "Default")
      (node (ref "CART1") (pin "L") (pinfunction "D3_L") (pintype "bidirectional"))
      (node (ref "U$3") (pin "13") (pinfunction "B5_13") (pintype "bidirectional"))
    )
    (net (code "84") (name "Net-(CART1-D4)") (class "Default")
      (node (ref "CART1") (pin "6") (pinfunction "D4_6") (pintype "bidirectional"))
      (node (ref "U$2") (pin "12") (pinfunction "B6_12") (pintype "bidirectional"))
    )
    (net (code "85") (name "Net-(CART1-D5)") (class "Default")
      (node (ref "CART1") (pin "7") (pinfunction "D5_7") (pintype "bidirectional"))
      (node (ref "U$2") (pin "14") (pinfunction "B4_14") (pintype "bidirectional"))
    )
    (net (code "86") (name "Net-(CART1-D6)") (class "Default")
      (node (ref "CART1") (pin "11") (pinfunction "D6_11") (pintype "bidirectional"))
      (node (ref "U$3") (pin "14") (pinfunction "B4_14") (pintype "bidirectional"))
    )
    (net (code "87") (name "Net-(CART1-D7)") (class "Default")
      (node (ref "CART1") (pin "M") (pinfunction "D7_M") (pintype "bidirectional"))
      (node (ref "U$3") (pin "15") (pinfunction "B3_15") (pintype "bidirectional"))
    )
    (net (code "88") (name "Net-(CART1-PHI2)") (class "Default")
      (node (ref "CART1") (pin "S") (pinfunction "PHI2_S") (pintype "output"))
      (node (ref "U$4") (pin "14") (pinfunction "B4_14") (pintype "bidirectional"))
    )
    (net (code "89") (name "Net-(CART1-RD4)") (class "Default")
      (node (ref "CART1") (pin "A") (pinfunction "RD4_A") (pintype "input"))
      (node (ref "U$1") (pin "12") (pinfunction "B6_12") (pintype "bidirectional"))
    )
    (net (code "90") (name "Net-(CART1-RD5)") (class "Default")
      (node (ref "CART1") (pin "14") (pinfunction "RD5_14") (pintype "input"))
      (node (ref "U$4") (pin "11") (pinfunction "B7_11") (pintype "bidirectional"))
    )
    (net (code "91") (name "Net-(CART1-R{slash}~{W})") (class "Default")
      (node (ref "CART1") (pin "R") (pinfunction "R/~{W}_R") (pintype "output"))
      (node (ref "U$4") (pin "12") (pinfunction "B6_12") (pintype "bidirectional"))
    )
    (net (code "92") (name "Net-(CART1-~{CCTL})") (class "Default")
      (node (ref "CART1") (pin "15") (pinfunction "~{CCTL}_15") (pintype "output"))
      (node (ref "U$4") (pin "13") (pinfunction "B5_13") (pintype "bidirectional"))
    )
    (net (code "93") (name "Net-(CART1-~{S4})") (class "Default")
      (node (ref "CART1") (pin "1") (pinfunction "~{S4}_1") (pintype "output"))
      (node (ref "U$1") (pin "11") (pinfunction "B7_11") (pintype "bidirectional"))
    )
    (net (code "94") (name "Net-(CART1-~{S5})") (class "Default")
      (node (ref "CART1") (pin "12") (pinfunction "~{S5}_12") (pintype "output"))
      (node (ref "U$3") (pin "16") (pinfunction "B2_16") (pintype "bidirectional"))
    )
    (net (code "95") (name "Net-(LED1-PadA)") (class "Default")
      (node (ref "LED1") (pin "A") (pinfunction "A_A") (pintype "passive"))
      (node (ref "R10") (pin "1") (pinfunction "1_1") (pintype "passive"))
    )
    (net (code "96") (name "Net-(S1-P)") (class "Default")
      (node (ref "R9") (pin "2") (pinfunction "2_2") (pintype "passive"))
      (node (ref "S1") (pin "1") (pinfunction "P_1") (pintype "passive"))
      (node (ref "U$5") (pin "129") (pinfunction "NCONFIG_129") (pintype "bidirectional"))
    )
    (net (code "97") (name "Net-(U$5-CLK0P)") (class "Default")
      (node (ref "U$5") (pin "27") (pinfunction "CLK0P_27") (pintype "bidirectional"))
      (node (ref "U$8") (pin "3") (pinfunction "OUT_3") (pintype "output"))
    )
    (net (code "98") (name "Net-(U$5-CONFIG_SEL)") (class "Default")
      (node (ref "R6") (pin "2") (pinfunction "2_2") (pintype "passive"))
      (node (ref "U$5") (pin "126") (pinfunction "CONFIG_SEL_126") (pintype "bidirectional"))
    )
    (net (code "99") (name "Net-(U$5-CONF_DONE)") (class "Default")
      (node (ref "R7") (pin "2") (pinfunction "2_2") (pintype "passive"))
      (node (ref "U$5") (pin "138") (pinfunction "CONF_DONE_138") (pintype "bidirectional"))
    )
    (net (code "100") (name "Net-(U$5-IO4_65)") (class "Default")
      (node (ref "U$5") (pin "65") (pinfunction "IO4_65_65") (pintype "bidirectional"))
      (node (ref "U$6") (pin "1") (pinfunction "CS_1") (pintype "input"))
    )
    (net (code "101") (name "Net-(U$5-IO4_66)") (class "Default")
      (node (ref "U$5") (pin "66") (pinfunction "IO4_66_66") (pintype "bidirectional"))
      (node (ref "U$6") (pin "2") (pinfunction "DATA_IN_2") (pintype "input"))
    )
    (net (code "102") (name "Net-(U$5-IO4_69)") (class "Default")
      (node (ref "U$5") (pin "69") (pinfunction "IO4_69_69") (pintype "bidirectional"))
      (node (ref "U$6") (pin "5") (pinfunction "SCLK_5") (pintype "input"))
    )
    (net (code "103") (name "Net-(U$5-IO4_70)") (class "Default")
      (node (ref "R11") (pin "2") (pinfunction "2_2") (pintype "passive"))
      (node (ref "U$5") (pin "70") (pinfunction "IO4_70_70") (pintype "bidirectional"))
      (node (ref "U$6") (pin "7") (pinfunction "DATA_OUT_7") (pintype "output"))
    )
    (net (code "104") (name "Net-(U$5-IO8_120)") (class "Default")
      (node (ref "LED1") (pin "C") (pinfunction "C_C") (pintype "passive"))
      (node (ref "U$5") (pin "120") (pinfunction "IO8_120_120") (pintype "bidirectional"))
    )
    (net (code "105") (name "Net-(U$5-NSTATUS)") (class "Default")
      (node (ref "R8") (pin "2") (pinfunction "2_2") (pintype "passive"))
      (node (ref "U$5") (pin "136") (pinfunction "NSTATUS_136") (pintype "bidirectional"))
    )
    (net (code "106") (name "TCK") (class "Default")
      (node (ref "JP1") (pin "1") (pinfunction "1_1") (pintype "passive"))
      (node (ref "R2") (pin "1") (pinfunction "1_1") (pintype "passive"))
      (node (ref "U$5") (pin "18") (pinfunction "TCK_18") (pintype "bidirectional"))
    )
    (net (code "107") (name "TDI") (class "Default")
      (node (ref "JP1") (pin "9") (pinfunction "9_9") (pintype "passive"))
      (node (ref "R4") (pin "2") (pinfunction "2_2") (pintype "passive"))
      (node (ref "U$5") (pin "19") (pinfunction "TDI_19") (pintype "bidirectional"))
    )
    (net (code "108") (name "TDO") (class "Default")
      (node (ref "JP1") (pin "3") (pinfunction "3_3") (pintype "passive"))
      (node (ref "U$5") (pin "20") (pinfunction "TDO_20") (pintype "bidirectional"))
    )
    (net (code "109") (name "TMS") (class "Default")
      (node (ref "JP1") (pin "5") (pinfunction "5_5") (pintype "passive"))
      (node (ref "R3") (pin "2") (pinfunction "2_2") (pintype "passive"))
      (node (ref "U$5") (pin "16") (pinfunction "TMS_16") (pintype "bidirectional"))
    )
    (net (code "110") (name "unconnected-(JP1-Pad6)") (class "Default")
      (node (ref "JP1") (pin "6") (pinfunction "6_6") (pintype "passive"))
    )
    (net (code "111") (name "unconnected-(JP1-Pad7)") (class "Default")
      (node (ref "JP1") (pin "7") (pinfunction "7_7") (pintype "passive"))
    )
    (net (code "112") (name "unconnected-(U$1-NC-Pad1)") (class "Default")
      (node (ref "U$1") (pin "1") (pinfunction "NC_1") (pintype "no_connect"))
    )
    (net (code "113") (name "unconnected-(U$2-NC-Pad1)") (class "Default")
      (node (ref "U$2") (pin "1") (pinfunction "NC_1") (pintype "no_connect"))
    )
    (net (code "114") (name "unconnected-(U$3-NC-Pad1)") (class "Default")
      (node (ref "U$3") (pin "1") (pinfunction "NC_1") (pintype "no_connect"))
    )
    (net (code "115") (name "unconnected-(U$4-NC-Pad1)") (class "Default")
      (node (ref "U$4") (pin "1") (pinfunction "NC_1") (pintype "no_connect"))
    )
    (net (code "116") (name "unconnected-(U$5-ADC_VREF-Pad5)") (class "Default")
      (node (ref "U$5") (pin "5") (pinfunction "ADC_VREF_5") (pintype "bidirectional"))
    )
    (net (code "117") (name "unconnected-(U$5-IO1A_6-Pad6)") (class "Default")
      (node (ref "U$5") (pin "6") (pinfunction "IO1A_6_6") (pintype "bidirectional"))
    )
    (net (code "118") (name "unconnected-(U$5-IO1A_7-Pad7)") (class "Default")
      (node (ref "U$5") (pin "7") (pinfunction "IO1A_7_7") (pintype "bidirectional"))
    )
    (net (code "119") (name "unconnected-(U$5-IO1A_8-Pad8)") (class "Default")
      (node (ref "U$5") (pin "8") (pinfunction "IO1A_8_8") (pintype "bidirectional"))
    )
    (net (code "120") (name "unconnected-(U$5-IO1A_10-Pad10)") (class "Default")
      (node (ref "U$5") (pin "10") (pinfunction "IO1A_10_10") (pintype "bidirectional"))
    )
    (net (code "121") (name "unconnected-(U$5-IO1A_11-Pad11)") (class "Default")
      (node (ref "U$5") (pin "11") (pinfunction "IO1A_11_11") (pintype "bidirectional"))
    )
    (net (code "122") (name "unconnected-(U$5-IO1A_12-Pad12)") (class "Default")
      (node (ref "U$5") (pin "12") (pinfunction "IO1A_12_12") (pintype "bidirectional"))
    )
    (net (code "123") (name "unconnected-(U$5-IO1A_13-Pad13)") (class "Default")
      (node (ref "U$5") (pin "13") (pinfunction "IO1A_13_13") (pintype "bidirectional"))
    )
    (net (code "124") (name "unconnected-(U$5-IO1A_14-Pad14)") (class "Default")
      (node (ref "U$5") (pin "14") (pinfunction "IO1A_14_14") (pintype "bidirectional"))
    )
    (net (code "125") (name "unconnected-(U$5-IO1B_21-Pad21)") (class "Default")
      (node (ref "U$5") (pin "21") (pinfunction "IO1B_21_21") (pintype "bidirectional"))
    )
    (net (code "126") (name "unconnected-(U$5-IO1B_22-Pad22)") (class "Default")
      (node (ref "U$5") (pin "22") (pinfunction "IO1B_22_22") (pintype "bidirectional"))
    )
    (net (code "127") (name "unconnected-(U$5-IO1B_24-Pad24)") (class "Default")
      (node (ref "U$5") (pin "24") (pinfunction "IO1B_24_24") (pintype "bidirectional"))
    )
    (net (code "128") (name "unconnected-(U$5-IO7_114-Pad114)") (class "Default")
      (node (ref "U$5") (pin "114") (pinfunction "IO7_114_114") (pintype "bidirectional"))
    )
    (net (code "129") (name "unconnected-(U$5-IO7_118-Pad118)") (class "Default")
      (node (ref "U$5") (pin "118") (pinfunction "IO7_118_118") (pintype "bidirectional"))
    )
    (net (code "130") (name "unconnected-(U$5-IO7_119-Pad119)") (class "Default")
      (node (ref "U$5") (pin "119") (pinfunction "IO7_119_119") (pintype "bidirectional"))
    )
    (net (code "131") (name "unconnected-(U$5-IO8_121-Pad121)") (class "Default")
      (node (ref "U$5") (pin "121") (pinfunction "IO8_121_121") (pintype "bidirectional"))
    )
    (net (code "132") (name "unconnected-(U$5-IO8_122-Pad122)") (class "Default")
      (node (ref "U$5") (pin "122") (pinfunction "IO8_122_122") (pintype "bidirectional"))
    )
    (net (code "133") (name "unconnected-(U$5-IO8_124-Pad124)") (class "Default")
      (node (ref "U$5") (pin "124") (pinfunction "IO8_124_124") (pintype "bidirectional"))
    )
    (net (code "134") (name "unconnected-(U$5-IO8_127-Pad127)") (class "Default")
      (node (ref "U$5") (pin "127") (pinfunction "IO8_127_127") (pintype "bidirectional"))
    )
    (net (code "135") (name "unconnected-(U$5-IO8_130-Pad130)") (class "Default")
      (node (ref "U$5") (pin "130") (pinfunction "IO8_130_130") (pintype "bidirectional"))
    )
    (net (code "136") (name "unconnected-(U$5-IO8_131-Pad131)") (class "Default")
      (node (ref "U$5") (pin "131") (pinfunction "IO8_131_131") (pintype "bidirectional"))
    )
    (net (code "137") (name "unconnected-(U$5-IO8_132-Pad132)") (class "Default")
      (node (ref "U$5") (pin "132") (pinfunction "IO8_132_132") (pintype "bidirectional"))
    )
    (net (code "138") (name "unconnected-(U$5-IO8_134-Pad134)") (class "Default")
      (node (ref "U$5") (pin "134") (pinfunction "IO8_134_134") (pintype "bidirectional"))
    )
    (net (code "139") (name "unconnected-(U$5-IO8_135-Pad135)") (class "Default")
      (node (ref "U$5") (pin "135") (pinfunction "IO8_135_135") (pintype "bidirectional"))
    )
    (net (code "140") (name "unconnected-(U$5-IO8_140-Pad140)") (class "Default")
      (node (ref "U$5") (pin "140") (pinfunction "IO8_140_140") (pintype "bidirectional"))
    )
    (net (code "141") (name "unconnected-(U$5-IO8_141-Pad141)") (class "Default")
      (node (ref "U$5") (pin "141") (pinfunction "IO8_141_141") (pintype "bidirectional"))
    )
    (net (code "142") (name "unconnected-(U$5-VREFB1-Pad17)") (class "Default")
      (node (ref "U$5") (pin "17") (pinfunction "VREFB1_17") (pintype "bidirectional"))
    )
    (net (code "143") (name "unconnected-(U$5-VREFB8-Pad123)") (class "Default")
      (node (ref "U$5") (pin "123") (pinfunction "VREFB8_123") (pintype "bidirectional"))
    )
    (net (code "144") (name "unconnected-(U$6-CARD_DETECT-PadCD)") (class "Default")
      (node (ref "U$6") (pin "CD") (pinfunction "CARD_DETECT_CD") (pintype "passive"))
    )
    (net (code "145") (name "unconnected-(U$6-COMMON_SW-PadGP3)") (class "Default")
      (node (ref "U$6") (pin "GP3") (pinfunction "COMMON_SW_GP3") (pintype "passive"))
    )
    (net (code "146") (name "unconnected-(U$6-DAT1-Pad8)") (class "Default")
      (node (ref "U$6") (pin "8") (pinfunction "DAT1_8") (pintype "bidirectional"))
    )
    (net (code "147") (name "unconnected-(U$6-DAT2-Pad9)") (class "Default")
      (node (ref "U$6") (pin "9") (pinfunction "DAT2_9") (pintype "bidirectional"))
    )
    (net (code "148") (name "unconnected-(U$6-WRITE_PROTECT-PadWP)") (class "Default")
      (node (ref "U$6") (pin "WP") (pinfunction "WRITE_PROTECT_WP") (pintype "passive"))
    )
    (net (code "149") (name "unconnected-(U$8-TRI-Pad1)") (class "Default")
      (node (ref "U$8") (pin "1") (pinfunction "TRI_1") (pintype "input"))
    )
  )
)
